# ExtenderCoco.net
KiCad netlist of a schematic drawn in EAGLE
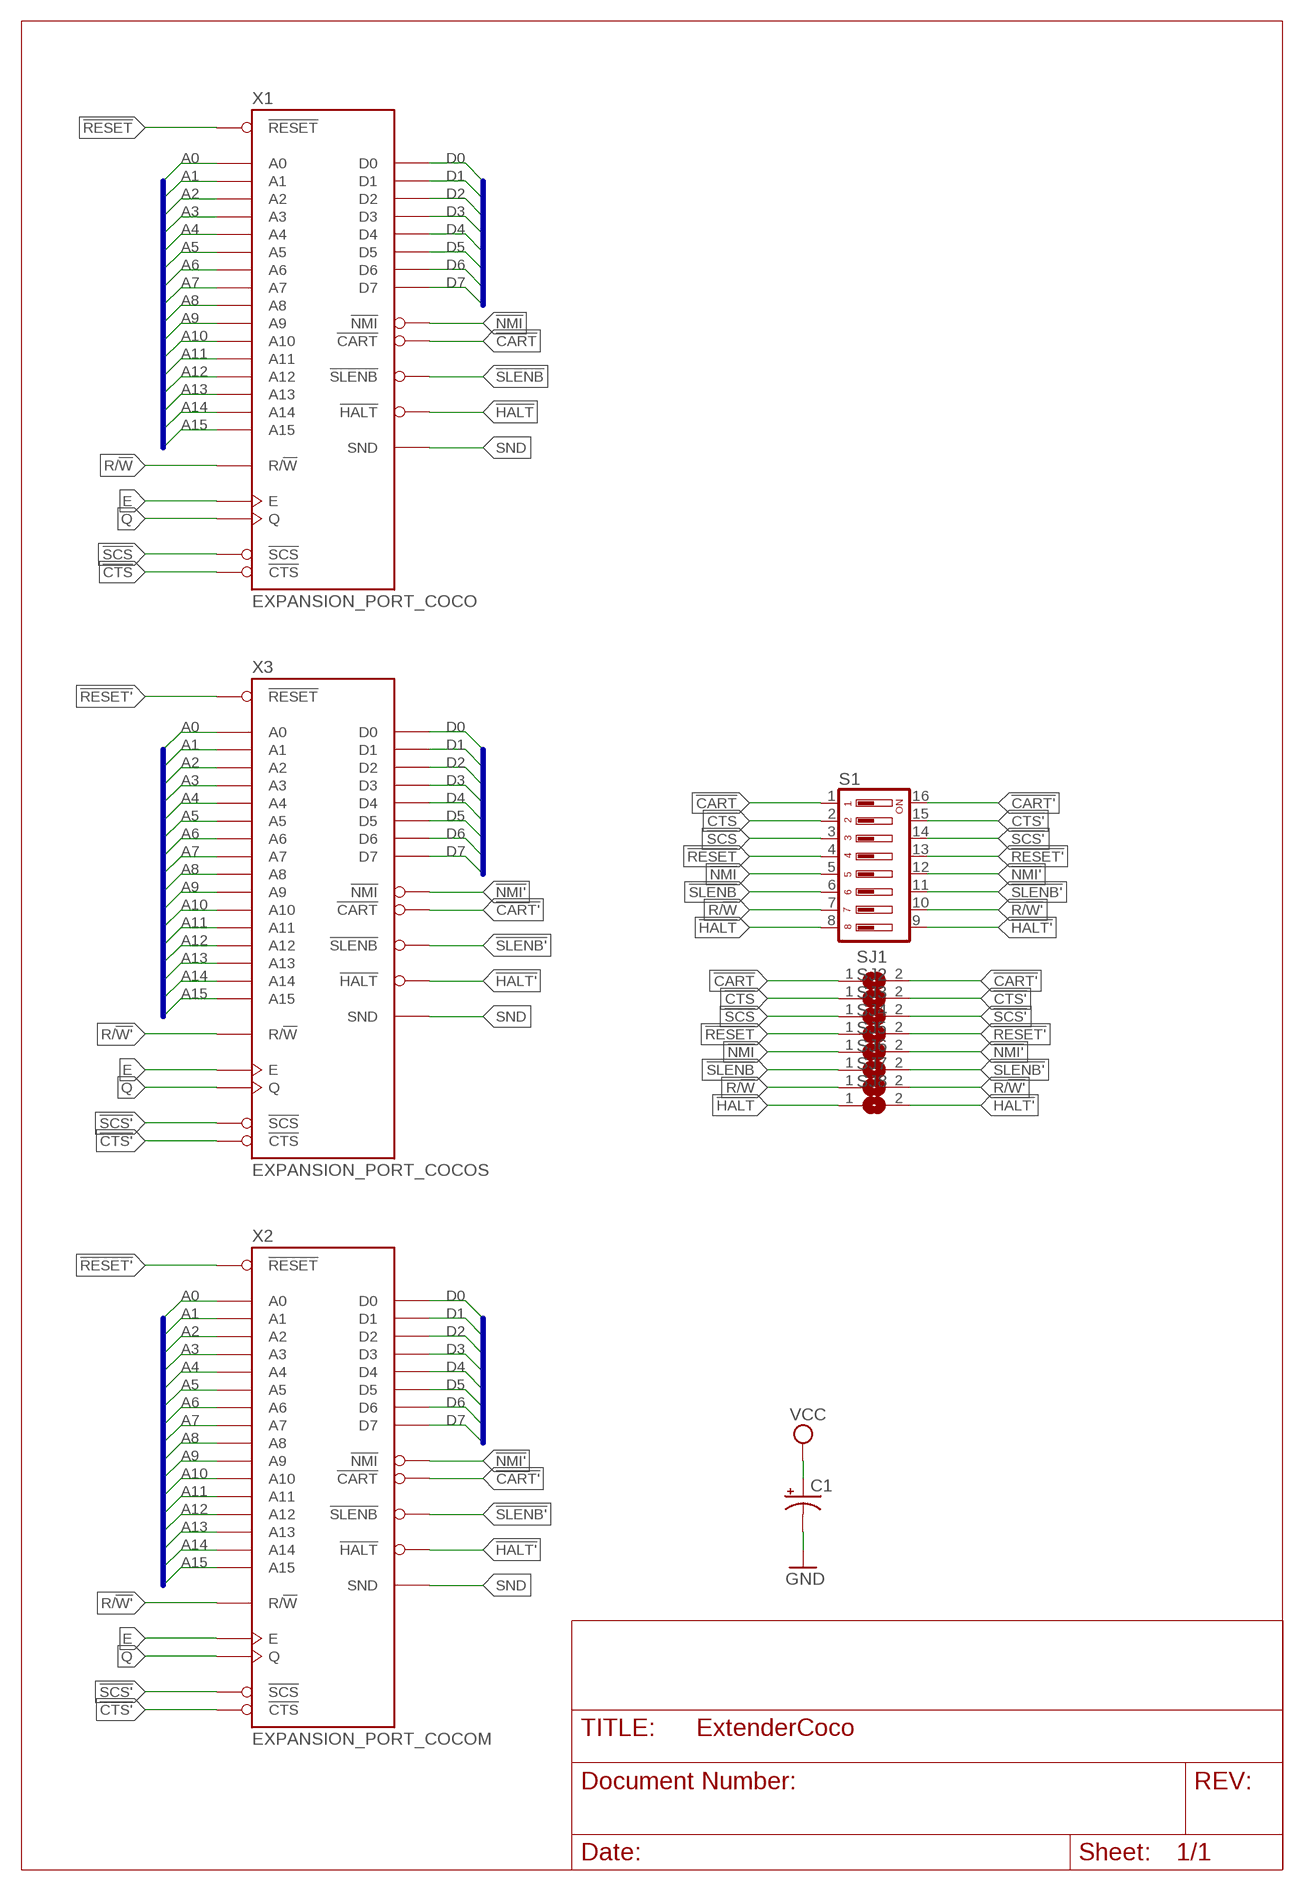
[diagram p0: schematic, sheet 1]

(export (version "E")
  (design (tool "Eeschema 10.0.6"))
  (components
    (comp (ref "C1")
      (value "CPOL-USE2-5")
      (footprint "eagle-import:E2-5")
      (libsource (lib "eagle-import") (part "CPOL-USE2-5"))
    )
    (comp (ref "S1")
      (value "DP08")
      (footprint "eagle-import:DP-08")
      (libsource (lib "eagle-import") (part "DP08"))
    )
    (comp (ref "SJ1") (value "SJ") (footprint "eagle-import:SJ") (libsource (lib "eagle-import") (part "SJ")))
    (comp (ref "SJ2") (value "SJ") (footprint "eagle-import:SJ") (libsource (lib "eagle-import") (part "SJ")))
    (comp (ref "SJ3") (value "SJ") (footprint "eagle-import:SJ") (libsource (lib "eagle-import") (part "SJ")))
    (comp (ref "SJ4") (value "SJ") (footprint "eagle-import:SJ") (libsource (lib "eagle-import") (part "SJ")))
    (comp (ref "SJ5") (value "SJ") (footprint "eagle-import:SJ") (libsource (lib "eagle-import") (part "SJ")))
    (comp (ref "SJ6") (value "SJ") (footprint "eagle-import:SJ") (libsource (lib "eagle-import") (part "SJ")))
    (comp (ref "SJ7") (value "SJ") (footprint "eagle-import:SJ") (libsource (lib "eagle-import") (part "SJ")))
    (comp (ref "SJ8") (value "SJ") (footprint "eagle-import:SJ") (libsource (lib "eagle-import") (part "SJ")))
    (comp (ref "X1")
      (value "EXPANSION_PORT_COCO")
      (footprint "eagle-import:MA20-2")
      (libsource (lib "eagle-import") (part "EXPANSION_PORT_COCO"))
    )
    (comp (ref "X2")
      (value "EXPANSION_PORT_COCOM")
      (footprint "eagle-import:FE20-2")
      (libsource (lib "eagle-import") (part "EXPANSION_PORT_COCOM"))
    )
    (comp (ref "X3")
      (value "EXPANSION_PORT_COCOS")
      (footprint "eagle-import:MA20-2_SHORT")
      (libsource (lib "eagle-import") (part "EXPANSION_PORT_COCOS"))
    )
  )
  (nets
    (net (code "1") (name "/A0") (class "Default")
      (node (ref "X1") (pin "19") (pinfunction "A0_19") (pintype "output"))
      (node (ref "X2") (pin "19") (pinfunction "A0_19") (pintype "output"))
      (node (ref "X3") (pin "19") (pinfunction "A0_19") (pintype "output"))
    )
    (net (code "2") (name "/A1") (class "Default")
      (node (ref "X1") (pin "20") (pinfunction "A1_20") (pintype "output"))
      (node (ref "X2") (pin "20") (pinfunction "A1_20") (pintype "output"))
      (node (ref "X3") (pin "20") (pinfunction "A1_20") (pintype "output"))
    )
    (net (code "3") (name "/A2") (class "Default")
      (node (ref "X1") (pin "21") (pinfunction "A2_21") (pintype "output"))
      (node (ref "X2") (pin "21") (pinfunction "A2_21") (pintype "output"))
      (node (ref "X3") (pin "21") (pinfunction "A2_21") (pintype "output"))
    )
    (net (code "4") (name "/A3") (class "Default")
      (node (ref "X1") (pin "22") (pinfunction "A3_22") (pintype "output"))
      (node (ref "X2") (pin "22") (pinfunction "A3_22") (pintype "output"))
      (node (ref "X3") (pin "22") (pinfunction "A3_22") (pintype "output"))
    )
    (net (code "5") (name "/A4") (class "Default")
      (node (ref "X1") (pin "23") (pinfunction "A4_23") (pintype "output"))
      (node (ref "X2") (pin "23") (pinfunction "A4_23") (pintype "output"))
      (node (ref "X3") (pin "23") (pinfunction "A4_23") (pintype "output"))
    )
    (net (code "6") (name "/A5") (class "Default")
      (node (ref "X1") (pin "24") (pinfunction "A5_24") (pintype "output"))
      (node (ref "X2") (pin "24") (pinfunction "A5_24") (pintype "output"))
      (node (ref "X3") (pin "24") (pinfunction "A5_24") (pintype "output"))
    )
    (net (code "7") (name "/A6") (class "Default")
      (node (ref "X1") (pin "25") (pinfunction "A6_25") (pintype "output"))
      (node (ref "X2") (pin "25") (pinfunction "A6_25") (pintype "output"))
      (node (ref "X3") (pin "25") (pinfunction "A6_25") (pintype "output"))
    )
    (net (code "8") (name "/A7") (class "Default")
      (node (ref "X1") (pin "26") (pinfunction "A7_26") (pintype "output"))
      (node (ref "X2") (pin "26") (pinfunction "A7_26") (pintype "output"))
      (node (ref "X3") (pin "26") (pinfunction "A7_26") (pintype "output"))
    )
    (net (code "9") (name "/A8") (class "Default")
      (node (ref "X1") (pin "27") (pinfunction "A8_27") (pintype "output"))
      (node (ref "X2") (pin "27") (pinfunction "A8_27") (pintype "output"))
      (node (ref "X3") (pin "27") (pinfunction "A8_27") (pintype "output"))
    )
    (net (code "10") (name "/A9") (class "Default")
      (node (ref "X1") (pin "28") (pinfunction "A9_28") (pintype "output"))
      (node (ref "X2") (pin "28") (pinfunction "A9_28") (pintype "output"))
      (node (ref "X3") (pin "28") (pinfunction "A9_28") (pintype "output"))
    )
    (net (code "11") (name "/A10") (class "Default")
      (node (ref "X1") (pin "29") (pinfunction "A10_29") (pintype "output"))
      (node (ref "X2") (pin "29") (pinfunction "A10_29") (pintype "output"))
      (node (ref "X3") (pin "29") (pinfunction "A10_29") (pintype "output"))
    )
    (net (code "12") (name "/A11") (class "Default")
      (node (ref "X1") (pin "30") (pinfunction "A11_30") (pintype "output"))
      (node (ref "X2") (pin "30") (pinfunction "A11_30") (pintype "output"))
      (node (ref "X3") (pin "30") (pinfunction "A11_30") (pintype "output"))
    )
    (net (code "13") (name "/A12") (class "Default")
      (node (ref "X1") (pin "31") (pinfunction "A12_31") (pintype "output"))
      (node (ref "X2") (pin "31") (pinfunction "A12_31") (pintype "output"))
      (node (ref "X3") (pin "31") (pinfunction "A12_31") (pintype "output"))
    )
    (net (code "14") (name "/A13") (class "Default")
      (node (ref "X1") (pin "37") (pinfunction "A13_37") (pintype "output"))
      (node (ref "X2") (pin "37") (pinfunction "A13_37") (pintype "output"))
      (node (ref "X3") (pin "37") (pinfunction "A13_37") (pintype "output"))
    )
    (net (code "15") (name "/A14") (class "Default")
      (node (ref "X1") (pin "38") (pinfunction "A14_38") (pintype "output"))
      (node (ref "X2") (pin "38") (pinfunction "A14_38") (pintype "output"))
      (node (ref "X3") (pin "38") (pinfunction "A14_38") (pintype "output"))
    )
    (net (code "16") (name "/A15") (class "Default")
      (node (ref "X1") (pin "39") (pinfunction "A15_39") (pintype "output"))
      (node (ref "X2") (pin "39") (pinfunction "A15_39") (pintype "output"))
      (node (ref "X3") (pin "39") (pinfunction "A15_39") (pintype "output"))
    )
    (net (code "17") (name "/D0") (class "Default")
      (node (ref "X1") (pin "10") (pinfunction "D0_10") (pintype "bidirectional"))
      (node (ref "X2") (pin "10") (pinfunction "D0_10") (pintype "bidirectional"))
      (node (ref "X3") (pin "10") (pinfunction "D0_10") (pintype "bidirectional"))
    )
    (net (code "18") (name "/D1") (class "Default")
      (node (ref "X1") (pin "11") (pinfunction "D1_11") (pintype "bidirectional"))
      (node (ref "X2") (pin "11") (pinfunction "D1_11") (pintype "bidirectional"))
      (node (ref "X3") (pin "11") (pinfunction "D1_11") (pintype "bidirectional"))
    )
    (net (code "19") (name "/D2") (class "Default")
      (node (ref "X1") (pin "12") (pinfunction "D2_12") (pintype "bidirectional"))
      (node (ref "X2") (pin "12") (pinfunction "D2_12") (pintype "bidirectional"))
      (node (ref "X3") (pin "12") (pinfunction "D2_12") (pintype "bidirectional"))
    )
    (net (code "20") (name "/D3") (class "Default")
      (node (ref "X1") (pin "13") (pinfunction "D3_13") (pintype "bidirectional"))
      (node (ref "X2") (pin "13") (pinfunction "D3_13") (pintype "bidirectional"))
      (node (ref "X3") (pin "13") (pinfunction "D3_13") (pintype "bidirectional"))
    )
    (net (code "21") (name "/D4") (class "Default")
      (node (ref "X1") (pin "14") (pinfunction "D4_14") (pintype "bidirectional"))
      (node (ref "X2") (pin "14") (pinfunction "D4_14") (pintype "bidirectional"))
      (node (ref "X3") (pin "14") (pinfunction "D4_14") (pintype "bidirectional"))
    )
    (net (code "22") (name "/D5") (class "Default")
      (node (ref "X1") (pin "15") (pinfunction "D5_15") (pintype "bidirectional"))
      (node (ref "X2") (pin "15") (pinfunction "D5_15") (pintype "bidirectional"))
      (node (ref "X3") (pin "15") (pinfunction "D5_15") (pintype "bidirectional"))
    )
    (net (code "23") (name "/D6") (class "Default")
      (node (ref "X1") (pin "16") (pinfunction "D6_16") (pintype "bidirectional"))
      (node (ref "X2") (pin "16") (pinfunction "D6_16") (pintype "bidirectional"))
      (node (ref "X3") (pin "16") (pinfunction "D6_16") (pintype "bidirectional"))
    )
    (net (code "24") (name "/D7") (class "Default")
      (node (ref "X1") (pin "17") (pinfunction "D7_17") (pintype "bidirectional"))
      (node (ref "X2") (pin "17") (pinfunction "D7_17") (pintype "bidirectional"))
      (node (ref "X3") (pin "17") (pinfunction "D7_17") (pintype "bidirectional"))
    )
    (net (code "25") (name "/R{slash}~{W'}") (class "Default")
      (node (ref "S1") (pin "10") (pinfunction "10_10") (pintype "passive"))
      (node (ref "SJ7") (pin "2") (pinfunction "2_2") (pintype "passive"))
      (node (ref "X2") (pin "18") (pinfunction "R/~{W}_18") (pintype "output"))
      (node (ref "X3") (pin "18") (pinfunction "R/~{W}_18") (pintype "output"))
    )
    (net (code "26") (name "/R{slash}~{W}") (class "Default")
      (node (ref "S1") (pin "7") (pinfunction "7_7") (pintype "passive"))
      (node (ref "SJ7") (pin "1") (pinfunction "1_1") (pintype "passive"))
      (node (ref "X1") (pin "18") (pinfunction "R/~{W}_18") (pintype "output"))
    )
    (net (code "27") (name "/~{CART'}") (class "Default")
      (node (ref "S1") (pin "16") (pinfunction "16_16") (pintype "passive"))
      (node (ref "SJ1") (pin "2") (pinfunction "2_2") (pintype "passive"))
      (node (ref "X2") (pin "8") (pinfunction "~{CART}_8") (pintype "open_collector"))
      (node (ref "X3") (pin "8") (pinfunction "~{CART}_8") (pintype "open_collector"))
    )
    (net (code "28") (name "/~{CART}") (class "Default")
      (node (ref "S1") (pin "1") (pinfunction "1_1") (pintype "passive"))
      (node (ref "SJ1") (pin "1") (pinfunction "1_1") (pintype "passive"))
      (node (ref "X1") (pin "8") (pinfunction "~{CART}_8") (pintype "open_collector"))
    )
    (net (code "29") (name "/~{CTS'}") (class "Default")
      (node (ref "S1") (pin "15") (pinfunction "15_15") (pintype "passive"))
      (node (ref "SJ2") (pin "2") (pinfunction "2_2") (pintype "passive"))
      (node (ref "X2") (pin "32") (pinfunction "~{CTS}_32") (pintype "output"))
      (node (ref "X3") (pin "32") (pinfunction "~{CTS}_32") (pintype "output"))
    )
    (net (code "30") (name "/~{CTS}") (class "Default")
      (node (ref "S1") (pin "2") (pinfunction "2_2") (pintype "passive"))
      (node (ref "SJ2") (pin "1") (pinfunction "1_1") (pintype "passive"))
      (node (ref "X1") (pin "32") (pinfunction "~{CTS}_32") (pintype "output"))
    )
    (net (code "31") (name "/~{HALT'}") (class "Default")
      (node (ref "S1") (pin "9") (pinfunction "9_9") (pintype "passive"))
      (node (ref "SJ8") (pin "2") (pinfunction "2_2") (pintype "passive"))
      (node (ref "X2") (pin "3") (pinfunction "~{HALT}_3") (pintype "open_collector"))
      (node (ref "X3") (pin "3") (pinfunction "~{HALT}_3") (pintype "open_collector"))
    )
    (net (code "32") (name "/~{HALT}") (class "Default")
      (node (ref "S1") (pin "8") (pinfunction "8_8") (pintype "passive"))
      (node (ref "SJ8") (pin "1") (pinfunction "1_1") (pintype "passive"))
      (node (ref "X1") (pin "3") (pinfunction "~{HALT}_3") (pintype "open_collector"))
    )
    (net (code "33") (name "/~{NMI'}") (class "Default")
      (node (ref "S1") (pin "12") (pinfunction "12_12") (pintype "passive"))
      (node (ref "SJ5") (pin "2") (pinfunction "2_2") (pintype "passive"))
      (node (ref "X2") (pin "4") (pinfunction "~{NMI}_4") (pintype "open_collector"))
      (node (ref "X3") (pin "4") (pinfunction "~{NMI}_4") (pintype "open_collector"))
    )
    (net (code "34") (name "/~{NMI}") (class "Default")
      (node (ref "S1") (pin "5") (pinfunction "5_5") (pintype "passive"))
      (node (ref "SJ5") (pin "1") (pinfunction "1_1") (pintype "passive"))
      (node (ref "X1") (pin "4") (pinfunction "~{NMI}_4") (pintype "open_collector"))
    )
    (net (code "35") (name "/~{RESET'}") (class "Default")
      (node (ref "S1") (pin "13") (pinfunction "13_13") (pintype "passive"))
      (node (ref "SJ4") (pin "2") (pinfunction "2_2") (pintype "passive"))
      (node (ref "X2") (pin "5") (pinfunction "~{RESET}_5") (pintype "open_collector"))
      (node (ref "X3") (pin "5") (pinfunction "~{RESET}_5") (pintype "open_collector"))
    )
    (net (code "36") (name "/~{RESET}") (class "Default")
      (node (ref "S1") (pin "4") (pinfunction "4_4") (pintype "passive"))
      (node (ref "SJ4") (pin "1") (pinfunction "1_1") (pintype "passive"))
      (node (ref "X1") (pin "5") (pinfunction "~{RESET}_5") (pintype "open_collector"))
    )
    (net (code "37") (name "/~{SCS'}") (class "Default")
      (node (ref "S1") (pin "14") (pinfunction "14_14") (pintype "passive"))
      (node (ref "SJ3") (pin "2") (pinfunction "2_2") (pintype "passive"))
      (node (ref "X2") (pin "36") (pinfunction "~{SCS}_36") (pintype "output"))
      (node (ref "X3") (pin "36") (pinfunction "~{SCS}_36") (pintype "output"))
    )
    (net (code "38") (name "/~{SCS}") (class "Default")
      (node (ref "S1") (pin "3") (pinfunction "3_3") (pintype "passive"))
      (node (ref "SJ3") (pin "1") (pinfunction "1_1") (pintype "passive"))
      (node (ref "X1") (pin "36") (pinfunction "~{SCS}_36") (pintype "output"))
    )
    (net (code "39") (name "/~{SLENB'}") (class "Default")
      (node (ref "S1") (pin "11") (pinfunction "11_11") (pintype "passive"))
      (node (ref "SJ6") (pin "2") (pinfunction "2_2") (pintype "passive"))
      (node (ref "X2") (pin "40") (pinfunction "~{SLENB}_40") (pintype "open_collector"))
      (node (ref "X3") (pin "40") (pinfunction "~{SLENB}_40") (pintype "open_collector"))
    )
    (net (code "40") (name "/~{SLENB}") (class "Default")
      (node (ref "S1") (pin "6") (pinfunction "6_6") (pintype "passive"))
      (node (ref "SJ6") (pin "1") (pinfunction "1_1") (pintype "passive"))
      (node (ref "X1") (pin "40") (pinfunction "~{SLENB}_40") (pintype "open_collector"))
    )
    (net (code "41") (name "E") (class "Default")
      (node (ref "X1") (pin "6") (pinfunction "E_6") (pintype "output"))
      (node (ref "X2") (pin "6") (pinfunction "E_6") (pintype "output"))
      (node (ref "X3") (pin "6") (pinfunction "E_6") (pintype "output"))
    )
    (net (code "42") (name "GND") (class "Default")
      (node (ref "C1") (pin "-") (pinfunction "-_-") (pintype "passive"))
    )
    (net (code "43") (name "Q") (class "Default")
      (node (ref "X1") (pin "7") (pinfunction "Q_7") (pintype "output"))
      (node (ref "X2") (pin "7") (pinfunction "Q_7") (pintype "output"))
      (node (ref "X3") (pin "7") (pinfunction "Q_7") (pintype "output"))
    )
    (net (code "44") (name "SND") (class "Default")
      (node (ref "X1") (pin "35") (pinfunction "SND_35") (pintype "passive"))
      (node (ref "X2") (pin "35") (pinfunction "SND_35") (pintype "passive"))
      (node (ref "X3") (pin "35") (pinfunction "SND_35") (pintype "passive"))
    )
    (net (code "45") (name "VCC") (class "Default")
      (node (ref "C1") (pin "+") (pinfunction "+_+") (pintype "passive"))
    )
  )
)
